# SCH_fridge-door-alarm_2024-07-15.net
KiCad netlist of a schematic drawn in EasyEDA
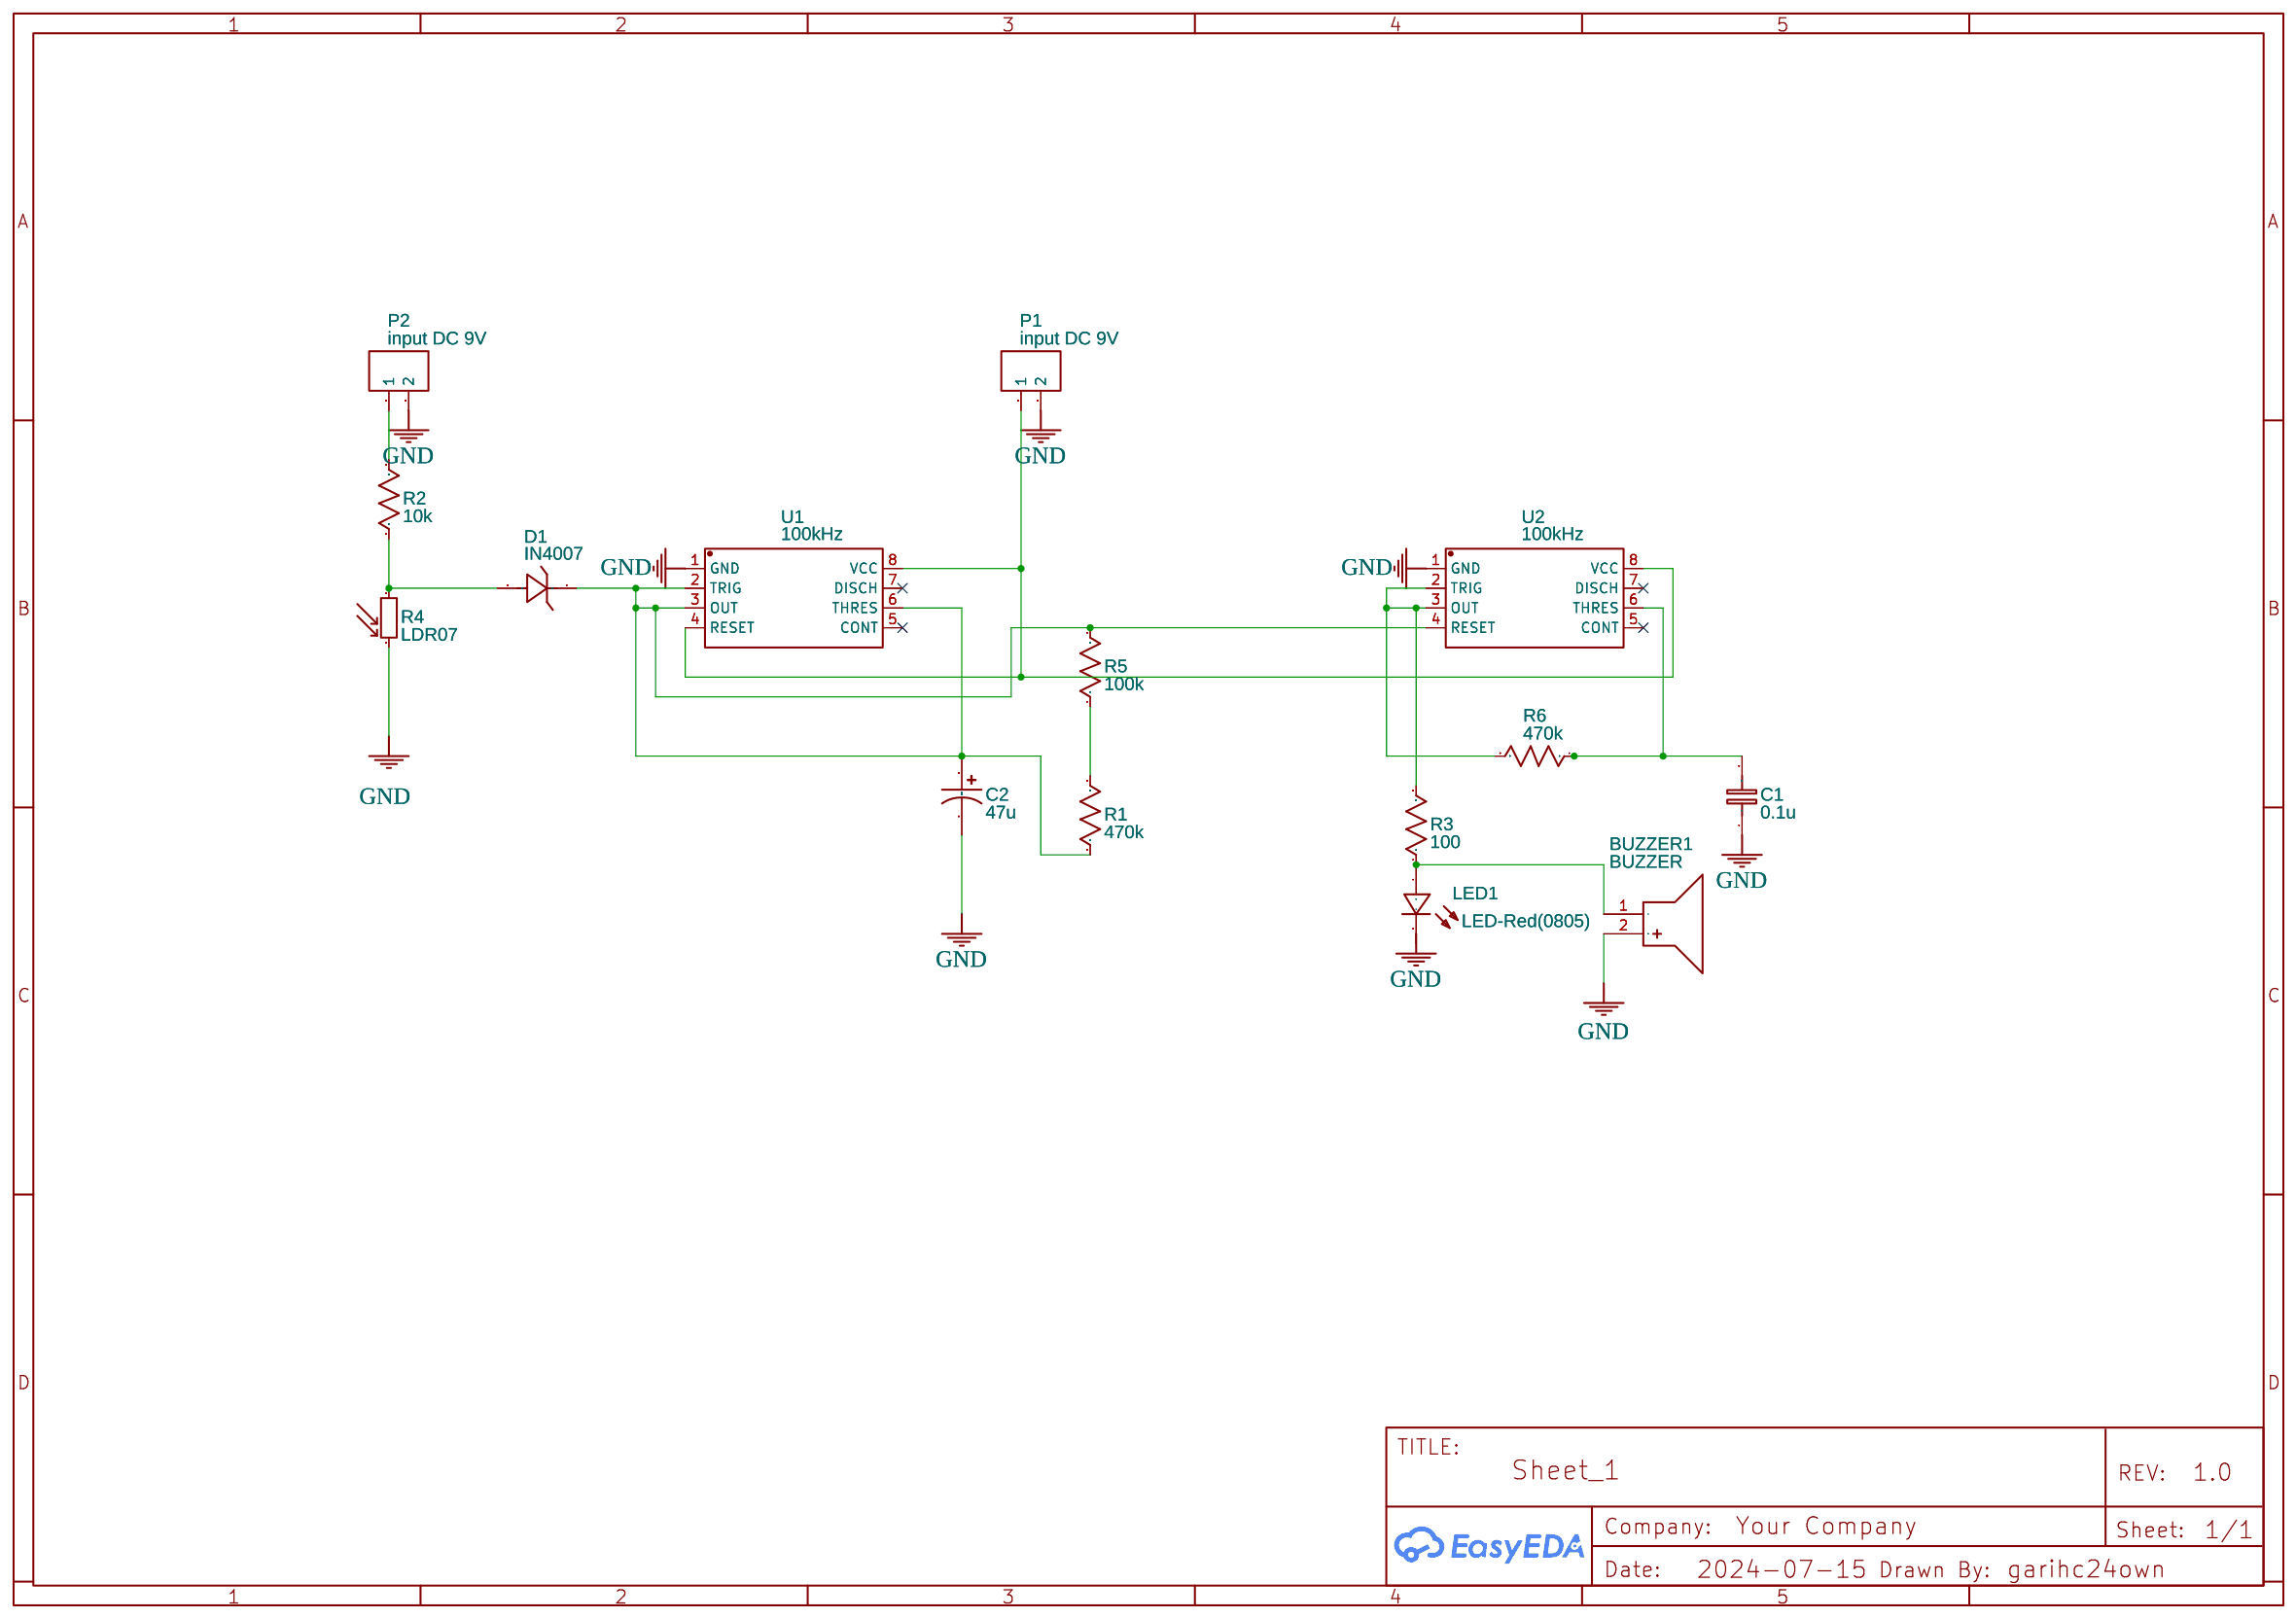
[diagram p0: schematic sheet]

(export (version "E")
  (design (tool "Eeschema 10.0.6"))
  (components
    (comp (ref "BUZZER1")
      (value "BUZZER")
      (fields (field (name "Manufacturer Part") "buzzer"))
      (libsource (lib "") (part "BUZZER"))
    )
    (comp (ref "C1") (value "0.1u") (libsource (lib "") (part "C_0603_EU")))
    (comp (ref "C2") (value "47u") (libsource (lib "") (part "C_Tan_SMD_A_US")))
    (comp (ref "D1") (value "IN4007") (libsource (lib "") (part "IN4007")))
    (comp (ref "LED1")
      (value "LED-Red(0805)")
      (fields
        (field (name "Manufacturer Part") "17-21SURC/S530-A2/TR8")
        (field (name "Manufacturer") "Everlight Elec")
      )
      (libsource (lib "") (part "LED-Red(0805)"))
    )
    (comp (ref "P1") (value "input DC 9V") (libsource (lib "") (part "CONN-TH_2P-P5.00")))
    (comp (ref "P2") (value "input DC 9V") (libsource (lib "") (part "CONN-TH_2P-P5.00")))
    (comp (ref "R1") (value "470k") (libsource (lib "") (part "R_0603_US")))
    (comp (ref "R2") (value "10k") (libsource (lib "") (part "R_AXIAL-0.4_US")))
    (comp (ref "R3") (value "100") (libsource (lib "") (part "R_0603_US")))
    (comp (ref "R4") (value "LDR07") (libsource (lib "") (part "LDR07")))
    (comp (ref "R5") (value "100k") (libsource (lib "") (part "R_0603_US")))
    (comp (ref "R6") (value "470k") (libsource (lib "") (part "R_0603_US_1")))
    (comp (ref "U1")
      (value "100kHz")
      (fields (field (name "Manufacturer Part") "NE555D") (field (name "Manufacturer") "TI(德州仪器)"))
      (libsource (lib "") (part "NE555D"))
    )
    (comp (ref "U2")
      (value "100kHz")
      (fields (field (name "Manufacturer Part") "NE555D") (field (name "Manufacturer") "TI(德州仪器)"))
      (libsource (lib "") (part "NE555D"))
    )
  )
  (nets
    (net (code "1") (name "GND") (class "Default")
      (node (ref "BUZZER1") (pin "2") (pinfunction "+_2") (pintype "unspecified"))
      (node (ref "C1") (pin "1") (pinfunction "1_1") (pintype "unspecified"))
      (node (ref "C2") (pin "2") (pinfunction "2_2") (pintype "unspecified"))
      (node (ref "P1") (pin "2") (pinfunction "2_2") (pintype "unspecified"))
      (node (ref "P2") (pin "2") (pinfunction "2_2") (pintype "unspecified"))
      (node (ref "R4") (pin "2") (pintype "unspecified"))
      (node (ref "U1") (pin "1") (pinfunction "GND_1") (pintype "unspecified"))
      (node (ref "U2") (pin "1") (pinfunction "GND_1") (pintype "unspecified"))
    )
    (net (code "2") (name "Net-(BUZZER1--)") (class "Default")
      (node (ref "BUZZER1") (pin "1") (pinfunction "-_1") (pintype "unspecified"))
      (node (ref "LED1") (pin "1") (pinfunction "+_1") (pintype "unspecified"))
      (node (ref "R3") (pin "1") (pinfunction "1_1") (pintype "unspecified"))
    )
    (net (code "3") (name "Net-(D1-A)") (class "Default")
      (node (ref "D1") (pin "2") (pinfunction "A_2") (pintype "unspecified"))
      (node (ref "R2") (pin "1") (pinfunction "1_1") (pintype "unspecified"))
      (node (ref "R4") (pin "1") (pintype "unspecified"))
    )
    (net (code "4") (name "Net-(D1-C)") (class "Default")
      (node (ref "C2") (pin "1") (pinfunction "1_1") (pintype "unspecified"))
      (node (ref "D1") (pin "1") (pinfunction "C_1") (pintype "unspecified"))
      (node (ref "R1") (pin "1") (pinfunction "1_1") (pintype "unspecified"))
      (node (ref "R5") (pin "2") (pinfunction "2_2") (pintype "unspecified"))
      (node (ref "U1") (pin "2") (pinfunction "TRIG_2") (pintype "unspecified"))
      (node (ref "U1") (pin "3") (pinfunction "OUT_3") (pintype "unspecified"))
      (node (ref "U1") (pin "6") (pinfunction "THRES_6") (pintype "unspecified"))
      (node (ref "U2") (pin "4") (pinfunction "RESET_4") (pintype "unspecified"))
    )
    (net (code "5") (name "Net-(P2-Pad1)") (class "Default")
      (node (ref "P2") (pin "1") (pinfunction "1_1") (pintype "unspecified"))
      (node (ref "R2") (pin "2") (pinfunction "2_2") (pintype "unspecified"))
    )
    (net (code "6") (name "Net-(R1-Pad2)") (class "Default")
      (node (ref "R1") (pin "2") (pinfunction "2_2") (pintype "unspecified"))
      (node (ref "R5") (pin "1") (pinfunction "1_1") (pintype "unspecified"))
    )
    (net (code "7") (name "Net-(U1-RESET)") (class "Default")
      (node (ref "P1") (pin "1") (pinfunction "1_1") (pintype "unspecified"))
      (node (ref "U1") (pin "4") (pinfunction "RESET_4") (pintype "unspecified"))
      (node (ref "U1") (pin "8") (pinfunction "VCC_8") (pintype "unspecified"))
      (node (ref "U2") (pin "8") (pinfunction "VCC_8") (pintype "unspecified"))
    )
    (net (code "8") (name "Net-(U2-OUT)") (class "Default")
      (node (ref "R3") (pin "2") (pinfunction "2_2") (pintype "unspecified"))
      (node (ref "R6") (pin "2") (pinfunction "2_2") (pintype "unspecified"))
      (node (ref "U2") (pin "2") (pinfunction "TRIG_2") (pintype "unspecified"))
      (node (ref "U2") (pin "3") (pinfunction "OUT_3") (pintype "unspecified"))
    )
    (net (code "9") (name "Net-(U2-THRES)") (class "Default")
      (node (ref "C1") (pin "2") (pinfunction "2_2") (pintype "unspecified"))
      (node (ref "R6") (pin "1") (pinfunction "1_1") (pintype "unspecified"))
      (node (ref "U2") (pin "6") (pinfunction "THRES_6") (pintype "unspecified"))
    )
    (net (code "10") (name "unconnected-(LED1---Pad2)") (class "Default")
      (node (ref "LED1") (pin "2") (pinfunction "-_2") (pintype "unspecified"))
    )
    (net (code "11") (name "unconnected-(U1-CONT-Pad5)") (class "Default")
      (node (ref "U1") (pin "5") (pinfunction "CONT_5") (pintype "unspecified+no_connect"))
    )
    (net (code "12") (name "unconnected-(U1-DISCH-Pad7)") (class "Default")
      (node (ref "U1") (pin "7") (pinfunction "DISCH_7") (pintype "unspecified+no_connect"))
    )
    (net (code "13") (name "unconnected-(U2-CONT-Pad5)") (class "Default")
      (node (ref "U2") (pin "5") (pinfunction "CONT_5") (pintype "unspecified+no_connect"))
    )
    (net (code "14") (name "unconnected-(U2-DISCH-Pad7)") (class "Default")
      (node (ref "U2") (pin "7") (pinfunction "DISCH_7") (pintype "unspecified+no_connect"))
    )
  )
)
